# ESPRELAYS.net
KiCad netlist of a schematic drawn in EAGLE
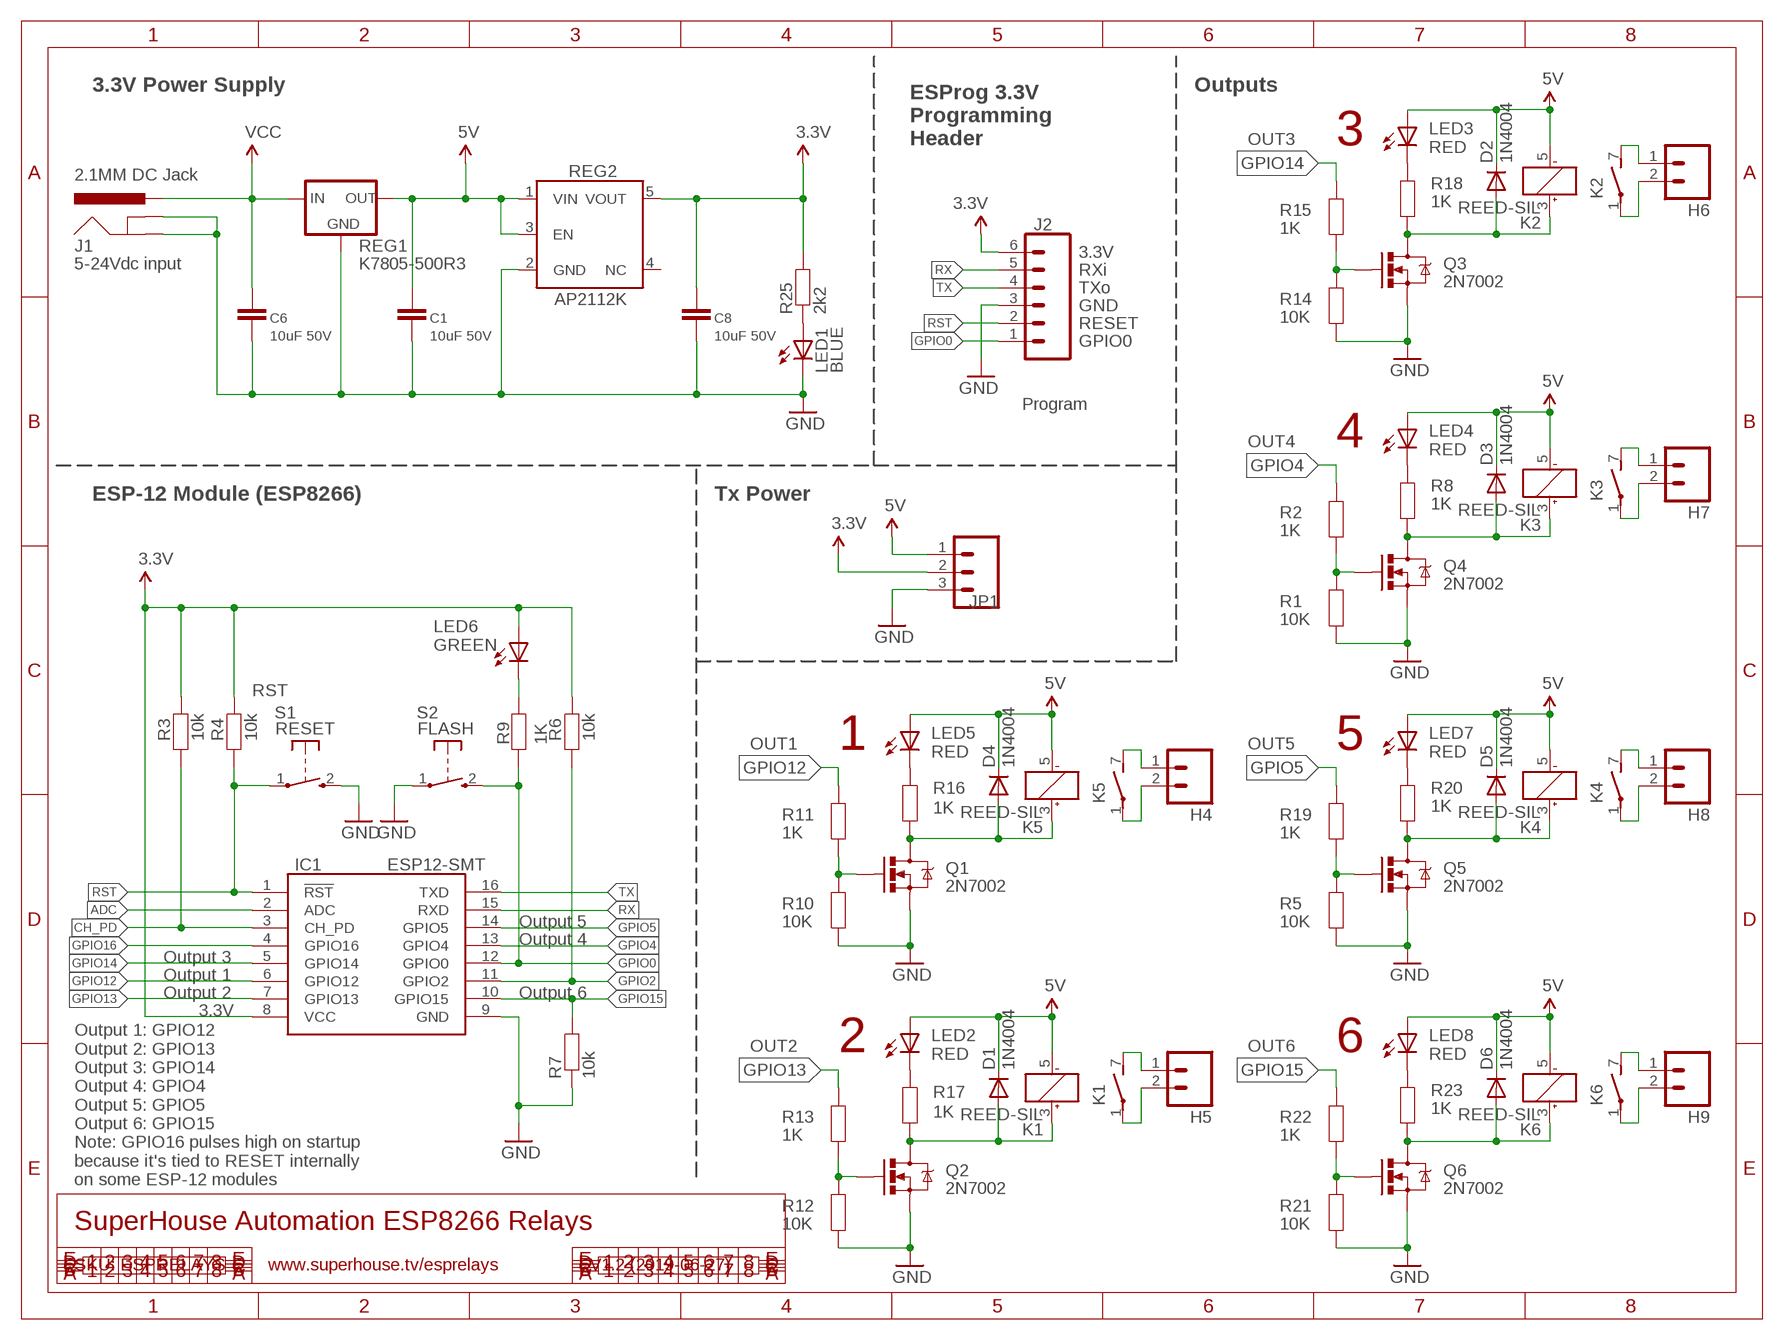
[diagram p0: schematic, sheet 1]

(export (version "E")
  (design (tool "Eeschema 10.0.6"))
  (components
    (comp (ref "C1")
      (value "10uF 50V")
      (footprint "eagle-import:C0805")
      (libsource (lib "eagle-import") (part "CAP0805"))
    )
    (comp (ref "C6")
      (value "10uF 50V")
      (footprint "eagle-import:C0805")
      (libsource (lib "eagle-import") (part "CAP0805"))
    )
    (comp (ref "C8")
      (value "10uF 50V")
      (footprint "eagle-import:C0805")
      (libsource (lib "eagle-import") (part "CAP0805"))
    )
    (comp (ref "D1")
      (value "1N4004")
      (footprint "eagle-import:SMA-DIODE")
      (libsource (lib "eagle-import") (part "DIODESMA"))
    )
    (comp (ref "D2")
      (value "1N4004")
      (footprint "eagle-import:SMA-DIODE")
      (libsource (lib "eagle-import") (part "DIODESMA"))
    )
    (comp (ref "D3")
      (value "1N4004")
      (footprint "eagle-import:SMA-DIODE")
      (libsource (lib "eagle-import") (part "DIODESMA"))
    )
    (comp (ref "D4")
      (value "1N4004")
      (footprint "eagle-import:SMA-DIODE")
      (libsource (lib "eagle-import") (part "DIODESMA"))
    )
    (comp (ref "D5")
      (value "1N4004")
      (footprint "eagle-import:SMA-DIODE")
      (libsource (lib "eagle-import") (part "DIODESMA"))
    )
    (comp (ref "D6")
      (value "1N4004")
      (footprint "eagle-import:SMA-DIODE")
      (libsource (lib "eagle-import") (part "DIODESMA"))
    )
    (comp (ref "H4")
      (value "M02-PIN")
      (footprint "eagle-import:1X02-P")
      (libsource (lib "eagle-import") (part "M02-PIN"))
    )
    (comp (ref "H5")
      (value "M02-PIN")
      (footprint "eagle-import:1X02-P")
      (libsource (lib "eagle-import") (part "M02-PIN"))
    )
    (comp (ref "H6")
      (value "M02-PIN")
      (footprint "eagle-import:1X02-P")
      (libsource (lib "eagle-import") (part "M02-PIN"))
    )
    (comp (ref "H7")
      (value "M02-PIN")
      (footprint "eagle-import:1X02-P")
      (libsource (lib "eagle-import") (part "M02-PIN"))
    )
    (comp (ref "H8")
      (value "M02-PIN")
      (footprint "eagle-import:1X02-P")
      (libsource (lib "eagle-import") (part "M02-PIN"))
    )
    (comp (ref "H9")
      (value "M02-PIN")
      (footprint "eagle-import:1X02-P")
      (libsource (lib "eagle-import") (part "M02-PIN"))
    )
    (comp (ref "IC1")
      (value "ESP12-SMT")
      (footprint "eagle-import:ESP12")
      (libsource (lib "eagle-import") (part "ESP12-SMT"))
    )
    (comp (ref "J1")
      (value "2.1MM DC Jack")
      (footprint "eagle-import:POWER_JACK_SLOTS")
      (libsource (lib "eagle-import") (part "POWER_JACK-SLOTS"))
    )
    (comp (ref "J2")
      (value "Program")
      (footprint "eagle-import:1X06-S")
      (libsource (lib "eagle-import") (part "M06-SOCKET"))
    )
    (comp (ref "JP1")
      (value "M03-PLAIN")
      (footprint "eagle-import:1X03")
      (libsource (lib "eagle-import") (part "M03-PLAIN"))
    )
    (comp (ref "K1")
      (value "REED-SIL")
      (footprint "eagle-import:REED")
      (libsource (lib "eagle-import") (part "REED-SIL"))
    )
    (comp (ref "K2")
      (value "REED-SIL")
      (footprint "eagle-import:REED")
      (libsource (lib "eagle-import") (part "REED-SIL"))
    )
    (comp (ref "K3")
      (value "REED-SIL")
      (footprint "eagle-import:REED")
      (libsource (lib "eagle-import") (part "REED-SIL"))
    )
    (comp (ref "K4")
      (value "REED-SIL")
      (footprint "eagle-import:REED")
      (libsource (lib "eagle-import") (part "REED-SIL"))
    )
    (comp (ref "K5")
      (value "REED-SIL")
      (footprint "eagle-import:REED")
      (libsource (lib "eagle-import") (part "REED-SIL"))
    )
    (comp (ref "K6")
      (value "REED-SIL")
      (footprint "eagle-import:REED")
      (libsource (lib "eagle-import") (part "REED-SIL"))
    )
    (comp (ref "LED1")
      (value "BLUE")
      (footprint "eagle-import:LED-0603")
      (libsource (lib "eagle-import") (part "LED0603"))
    )
    (comp (ref "LED2")
      (value "RED")
      (footprint "eagle-import:LED-0603")
      (libsource (lib "eagle-import") (part "LED0603"))
    )
    (comp (ref "LED3")
      (value "RED")
      (footprint "eagle-import:LED-0603")
      (libsource (lib "eagle-import") (part "LED0603"))
    )
    (comp (ref "LED4")
      (value "RED")
      (footprint "eagle-import:LED-0603")
      (libsource (lib "eagle-import") (part "LED0603"))
    )
    (comp (ref "LED5")
      (value "RED")
      (footprint "eagle-import:LED-0603")
      (libsource (lib "eagle-import") (part "LED0603"))
    )
    (comp (ref "LED6")
      (value "GREEN")
      (footprint "eagle-import:LED-0603")
      (libsource (lib "eagle-import") (part "LED0603"))
    )
    (comp (ref "LED7")
      (value "RED")
      (footprint "eagle-import:LED-0603")
      (libsource (lib "eagle-import") (part "LED0603"))
    )
    (comp (ref "LED8")
      (value "RED")
      (footprint "eagle-import:LED-0603")
      (libsource (lib "eagle-import") (part "LED0603"))
    )
    (comp (ref "Q1")
      (value "2N7002")
      (footprint "eagle-import:SOT23-3")
      (libsource (lib "eagle-import") (part "MOSFET-NCHANNELSMD"))
    )
    (comp (ref "Q2")
      (value "2N7002")
      (footprint "eagle-import:SOT23-3")
      (libsource (lib "eagle-import") (part "MOSFET-NCHANNELSMD"))
    )
    (comp (ref "Q3")
      (value "2N7002")
      (footprint "eagle-import:SOT23-3")
      (libsource (lib "eagle-import") (part "MOSFET-NCHANNELSMD"))
    )
    (comp (ref "Q4")
      (value "2N7002")
      (footprint "eagle-import:SOT23-3")
      (libsource (lib "eagle-import") (part "MOSFET-NCHANNELSMD"))
    )
    (comp (ref "Q5")
      (value "2N7002")
      (footprint "eagle-import:SOT23-3")
      (libsource (lib "eagle-import") (part "MOSFET-NCHANNELSMD"))
    )
    (comp (ref "Q6")
      (value "2N7002")
      (footprint "eagle-import:SOT23-3")
      (libsource (lib "eagle-import") (part "MOSFET-NCHANNELSMD"))
    )
    (comp (ref "R1")
      (value "10K")
      (footprint "eagle-import:R0603")
      (libsource (lib "eagle-import") (part "RESISTOR0603"))
    )
    (comp (ref "R2")
      (value "1K")
      (footprint "eagle-import:R0603")
      (libsource (lib "eagle-import") (part "RESISTOR0603"))
    )
    (comp (ref "R3")
      (value "10k")
      (footprint "eagle-import:R0603")
      (libsource (lib "eagle-import") (part "RESISTOR0603"))
    )
    (comp (ref "R4")
      (value "10k")
      (footprint "eagle-import:R0603")
      (libsource (lib "eagle-import") (part "RESISTOR0603"))
    )
    (comp (ref "R5")
      (value "10K")
      (footprint "eagle-import:R0603")
      (libsource (lib "eagle-import") (part "RESISTOR0603"))
    )
    (comp (ref "R6")
      (value "10k")
      (footprint "eagle-import:R0603")
      (libsource (lib "eagle-import") (part "RESISTOR0603"))
    )
    (comp (ref "R7")
      (value "10k")
      (footprint "eagle-import:R0603")
      (libsource (lib "eagle-import") (part "RESISTOR0603"))
    )
    (comp (ref "R8")
      (value "1K")
      (footprint "eagle-import:R0603")
      (libsource (lib "eagle-import") (part "RESISTOR0603"))
    )
    (comp (ref "R9")
      (value "1K")
      (footprint "eagle-import:R0603")
      (libsource (lib "eagle-import") (part "RESISTOR0603"))
    )
    (comp (ref "R10")
      (value "10K")
      (footprint "eagle-import:R0603")
      (libsource (lib "eagle-import") (part "RESISTOR0603"))
    )
    (comp (ref "R11")
      (value "1K")
      (footprint "eagle-import:R0603")
      (libsource (lib "eagle-import") (part "RESISTOR0603"))
    )
    (comp (ref "R12")
      (value "10K")
      (footprint "eagle-import:R0603")
      (libsource (lib "eagle-import") (part "RESISTOR0603"))
    )
    (comp (ref "R13")
      (value "1K")
      (footprint "eagle-import:R0603")
      (libsource (lib "eagle-import") (part "RESISTOR0603"))
    )
    (comp (ref "R14")
      (value "10K")
      (footprint "eagle-import:R0603")
      (libsource (lib "eagle-import") (part "RESISTOR0603"))
    )
    (comp (ref "R15")
      (value "1K")
      (footprint "eagle-import:R0603")
      (libsource (lib "eagle-import") (part "RESISTOR0603"))
    )
    (comp (ref "R16")
      (value "1K")
      (footprint "eagle-import:R0603")
      (libsource (lib "eagle-import") (part "RESISTOR0603"))
    )
    (comp (ref "R17")
      (value "1K")
      (footprint "eagle-import:R0603")
      (libsource (lib "eagle-import") (part "RESISTOR0603"))
    )
    (comp (ref "R18")
      (value "1K")
      (footprint "eagle-import:R0603")
      (libsource (lib "eagle-import") (part "RESISTOR0603"))
    )
    (comp (ref "R19")
      (value "1K")
      (footprint "eagle-import:R0603")
      (libsource (lib "eagle-import") (part "RESISTOR0603"))
    )
    (comp (ref "R20")
      (value "1K")
      (footprint "eagle-import:R0603")
      (libsource (lib "eagle-import") (part "RESISTOR0603"))
    )
    (comp (ref "R21")
      (value "10K")
      (footprint "eagle-import:R0603")
      (libsource (lib "eagle-import") (part "RESISTOR0603"))
    )
    (comp (ref "R22")
      (value "1K")
      (footprint "eagle-import:R0603")
      (libsource (lib "eagle-import") (part "RESISTOR0603"))
    )
    (comp (ref "R23")
      (value "1K")
      (footprint "eagle-import:R0603")
      (libsource (lib "eagle-import") (part "RESISTOR0603"))
    )
    (comp (ref "R25")
      (value "2k2")
      (footprint "eagle-import:R0603")
      (libsource (lib "eagle-import") (part "RESISTOR0603"))
    )
    (comp (ref "REG1")
      (value "K7805-500R3")
      (footprint "eagle-import:K78XX-500R3")
      (libsource (lib "eagle-import") (part "K78XX-500R3"))
    )
    (comp (ref "REG2")
      (value "AP2112KSOT25")
      (footprint "eagle-import:SOT23-5")
      (libsource (lib "eagle-import") (part "AP2112KSOT25"))
    )
    (comp (ref "S1")
      (value "RESET")
      (footprint "eagle-import:TACTILE_SMD_3X4X2")
      (libsource (lib "eagle-import") (part "TAC_SWITCH_2PINSMT"))
    )
    (comp (ref "S2")
      (value "FLASH")
      (footprint "eagle-import:TACTILE_SMD_3X4X2")
      (libsource (lib "eagle-import") (part "TAC_SWITCH_2PINSMT"))
    )
  )
  (nets
    (net (code "1") (name "/OUT1") (class "Default")
      (node (ref "D4") (pin "A") (pinfunction "A_A") (pintype "passive"))
      (node (ref "K5") (pin "3") (pinfunction "+_3") (pintype "passive"))
      (node (ref "Q1") (pin "3") (pinfunction "D_3") (pintype "passive"))
      (node (ref "R16") (pin "2") (pinfunction "2_2") (pintype "passive"))
    )
    (net (code "2") (name "/OUT2") (class "Default")
      (node (ref "D1") (pin "A") (pinfunction "A_A") (pintype "passive"))
      (node (ref "K1") (pin "3") (pinfunction "+_3") (pintype "passive"))
      (node (ref "Q2") (pin "3") (pinfunction "D_3") (pintype "passive"))
      (node (ref "R17") (pin "2") (pinfunction "2_2") (pintype "passive"))
    )
    (net (code "3") (name "/OUT3") (class "Default")
      (node (ref "D2") (pin "A") (pinfunction "A_A") (pintype "passive"))
      (node (ref "K2") (pin "3") (pinfunction "+_3") (pintype "passive"))
      (node (ref "Q3") (pin "3") (pinfunction "D_3") (pintype "passive"))
      (node (ref "R18") (pin "2") (pinfunction "2_2") (pintype "passive"))
    )
    (net (code "4") (name "/OUT4") (class "Default")
      (node (ref "D3") (pin "A") (pinfunction "A_A") (pintype "passive"))
      (node (ref "K3") (pin "3") (pinfunction "+_3") (pintype "passive"))
      (node (ref "Q4") (pin "3") (pinfunction "D_3") (pintype "passive"))
      (node (ref "R8") (pin "2") (pinfunction "2_2") (pintype "passive"))
    )
    (net (code "5") (name "/OUT5") (class "Default")
      (node (ref "D5") (pin "A") (pinfunction "A_A") (pintype "passive"))
      (node (ref "K4") (pin "3") (pinfunction "+_3") (pintype "passive"))
      (node (ref "Q5") (pin "3") (pinfunction "D_3") (pintype "passive"))
      (node (ref "R20") (pin "2") (pinfunction "2_2") (pintype "passive"))
    )
    (net (code "6") (name "/OUT6") (class "Default")
      (node (ref "D6") (pin "A") (pinfunction "A_A") (pintype "passive"))
      (node (ref "K6") (pin "3") (pinfunction "+_3") (pintype "passive"))
      (node (ref "Q6") (pin "3") (pinfunction "D_3") (pintype "passive"))
      (node (ref "R23") (pin "2") (pinfunction "2_2") (pintype "passive"))
    )
    (net (code "7") (name "3.3V") (class "Default")
      (node (ref "C8") (pin "1") (pinfunction "1_1") (pintype "passive"))
      (node (ref "IC1") (pin "8") (pinfunction "VCC_8") (pintype "power_in"))
      (node (ref "J2") (pin "6") (pinfunction "6_6") (pintype "passive"))
      (node (ref "JP1") (pin "2") (pinfunction "2_2") (pintype "passive"))
      (node (ref "LED6") (pin "A") (pinfunction "A_A") (pintype "passive"))
      (node (ref "R25") (pin "2") (pinfunction "2_2") (pintype "passive"))
      (node (ref "R3") (pin "2") (pinfunction "2_2") (pintype "passive"))
      (node (ref "R4") (pin "2") (pinfunction "2_2") (pintype "passive"))
      (node (ref "R6") (pin "2") (pinfunction "2_2") (pintype "passive"))
      (node (ref "REG2") (pin "5") (pinfunction "VOUT_5") (pintype "bidirectional"))
    )
    (net (code "8") (name "5V") (class "Default")
      (node (ref "C1") (pin "1") (pinfunction "1_1") (pintype "passive"))
      (node (ref "D1") (pin "C") (pinfunction "C_C") (pintype "passive"))
      (node (ref "D2") (pin "C") (pinfunction "C_C") (pintype "passive"))
      (node (ref "D3") (pin "C") (pinfunction "C_C") (pintype "passive"))
      (node (ref "D4") (pin "C") (pinfunction "C_C") (pintype "passive"))
      (node (ref "D5") (pin "C") (pinfunction "C_C") (pintype "passive"))
      (node (ref "D6") (pin "C") (pinfunction "C_C") (pintype "passive"))
      (node (ref "JP1") (pin "1") (pinfunction "1_1") (pintype "passive"))
      (node (ref "K1") (pin "5") (pinfunction "-_5") (pintype "passive"))
      (node (ref "K2") (pin "5") (pinfunction "-_5") (pintype "passive"))
      (node (ref "K3") (pin "5") (pinfunction "-_5") (pintype "passive"))
      (node (ref "K4") (pin "5") (pinfunction "-_5") (pintype "passive"))
      (node (ref "K5") (pin "5") (pinfunction "-_5") (pintype "passive"))
      (node (ref "K6") (pin "5") (pinfunction "-_5") (pintype "passive"))
      (node (ref "LED2") (pin "A") (pinfunction "A_A") (pintype "passive"))
      (node (ref "LED3") (pin "A") (pinfunction "A_A") (pintype "passive"))
      (node (ref "LED4") (pin "A") (pinfunction "A_A") (pintype "passive"))
      (node (ref "LED5") (pin "A") (pinfunction "A_A") (pintype "passive"))
      (node (ref "LED7") (pin "A") (pinfunction "A_A") (pintype "passive"))
      (node (ref "LED8") (pin "A") (pinfunction "A_A") (pintype "passive"))
      (node (ref "REG1") (pin "3") (pinfunction "OUT_3") (pintype "output"))
      (node (ref "REG2") (pin "1") (pinfunction "VIN_1") (pintype "bidirectional"))
      (node (ref "REG2") (pin "3") (pinfunction "EN_3") (pintype "bidirectional"))
    )
    (net (code "9") (name "ADC") (class "Default")
      (node (ref "IC1") (pin "2") (pinfunction "ADC_2") (pintype "input"))
    )
    (net (code "10") (name "CH_PD") (class "Default")
      (node (ref "IC1") (pin "3") (pinfunction "CH_PD_3") (pintype "input"))
      (node (ref "R3") (pin "1") (pinfunction "1_1") (pintype "passive"))
    )
    (net (code "11") (name "GND") (class "Default")
      (node (ref "C1") (pin "2") (pinfunction "2_2") (pintype "passive"))
      (node (ref "C6") (pin "2") (pinfunction "2_2") (pintype "passive"))
      (node (ref "C8") (pin "2") (pinfunction "2_2") (pintype "passive"))
      (node (ref "IC1") (pin "9") (pinfunction "GND_9") (pintype "power_in"))
      (node (ref "J1") (pin "GND") (pinfunction "GND_GND") (pintype "bidirectional"))
      (node (ref "J1") (pin "GNDBREAK") (pinfunction "GNDBREAK_GNDBREAK") (pintype "bidirectional"))
      (node (ref "J2") (pin "3") (pinfunction "3_3") (pintype "passive"))
      (node (ref "JP1") (pin "3") (pinfunction "3_3") (pintype "passive"))
      (node (ref "LED1") (pin "C") (pinfunction "C_C") (pintype "passive"))
      (node (ref "Q1") (pin "2") (pinfunction "S_2") (pintype "passive"))
      (node (ref "Q2") (pin "2") (pinfunction "S_2") (pintype "passive"))
      (node (ref "Q3") (pin "2") (pinfunction "S_2") (pintype "passive"))
      (node (ref "Q4") (pin "2") (pinfunction "S_2") (pintype "passive"))
      (node (ref "Q5") (pin "2") (pinfunction "S_2") (pintype "passive"))
      (node (ref "Q6") (pin "2") (pinfunction "S_2") (pintype "passive"))
      (node (ref "R1") (pin "1") (pinfunction "1_1") (pintype "passive"))
      (node (ref "R10") (pin "1") (pinfunction "1_1") (pintype "passive"))
      (node (ref "R12") (pin "1") (pinfunction "1_1") (pintype "passive"))
      (node (ref "R14") (pin "1") (pinfunction "1_1") (pintype "passive"))
      (node (ref "R21") (pin "1") (pinfunction "1_1") (pintype "passive"))
      (node (ref "R5") (pin "1") (pinfunction "1_1") (pintype "passive"))
      (node (ref "R7") (pin "1") (pinfunction "1_1") (pintype "passive"))
      (node (ref "REG1") (pin "2") (pinfunction "GND_2") (pintype "input"))
      (node (ref "REG2") (pin "2") (pinfunction "GND_2") (pintype "bidirectional"))
      (node (ref "S1") (pin "2") (pinfunction "S_2") (pintype "passive"))
      (node (ref "S2") (pin "1") (pinfunction "P_1") (pintype "passive"))
    )
    (net (code "12") (name "GPIO0") (class "Default")
      (node (ref "IC1") (pin "12") (pinfunction "GPIO0_12") (pintype "bidirectional"))
      (node (ref "J2") (pin "1") (pinfunction "1_1") (pintype "passive"))
      (node (ref "R9") (pin "2") (pinfunction "2_2") (pintype "passive"))
      (node (ref "S2") (pin "2") (pinfunction "S_2") (pintype "passive"))
    )
    (net (code "13") (name "GPIO2") (class "Default")
      (node (ref "IC1") (pin "11") (pinfunction "GPIO2_11") (pintype "bidirectional"))
      (node (ref "R6") (pin "1") (pinfunction "1_1") (pintype "passive"))
    )
    (net (code "14") (name "GPIO4") (class "Default")
      (node (ref "IC1") (pin "13") (pinfunction "GPIO4_13") (pintype "bidirectional"))
      (node (ref "R2") (pin "2") (pinfunction "2_2") (pintype "passive"))
    )
    (net (code "15") (name "GPIO5") (class "Default")
      (node (ref "IC1") (pin "14") (pinfunction "GPIO5_14") (pintype "bidirectional"))
      (node (ref "R19") (pin "2") (pinfunction "2_2") (pintype "passive"))
    )
    (net (code "16") (name "GPIO12") (class "Default")
      (node (ref "IC1") (pin "6") (pinfunction "GPIO12_6") (pintype "bidirectional"))
      (node (ref "R11") (pin "2") (pinfunction "2_2") (pintype "passive"))
    )
    (net (code "17") (name "GPIO13") (class "Default")
      (node (ref "IC1") (pin "7") (pinfunction "GPIO13_7") (pintype "bidirectional"))
      (node (ref "R13") (pin "2") (pinfunction "2_2") (pintype "passive"))
    )
    (net (code "18") (name "GPIO14") (class "Default")
      (node (ref "IC1") (pin "5") (pinfunction "GPIO14_5") (pintype "bidirectional"))
      (node (ref "R15") (pin "2") (pinfunction "2_2") (pintype "passive"))
    )
    (net (code "19") (name "GPIO15") (class "Default")
      (node (ref "IC1") (pin "10") (pinfunction "GPIO15_10") (pintype "bidirectional"))
      (node (ref "R22") (pin "2") (pinfunction "2_2") (pintype "passive"))
      (node (ref "R7") (pin "2") (pinfunction "2_2") (pintype "passive"))
    )
    (net (code "20") (name "GPIO16") (class "Default")
      (node (ref "IC1") (pin "4") (pinfunction "GPIO16_4") (pintype "bidirectional"))
    )
    (net (code "21") (name "Net-(K1B-P)") (class "Default")
      (node (ref "H5") (pin "2") (pinfunction "2_2") (pintype "passive"))
      (node (ref "K1") (pin "1") (pinfunction "P_1") (pintype "passive"))
    )
    (net (code "22") (name "Net-(K1B-S)") (class "Default")
      (node (ref "H5") (pin "1") (pinfunction "1_1") (pintype "passive"))
      (node (ref "K1") (pin "7") (pinfunction "S_7") (pintype "passive"))
    )
    (net (code "23") (name "Net-(K2B-P)") (class "Default")
      (node (ref "H6") (pin "2") (pinfunction "2_2") (pintype "passive"))
      (node (ref "K2") (pin "1") (pinfunction "P_1") (pintype "passive"))
    )
    (net (code "24") (name "Net-(K2B-S)") (class "Default")
      (node (ref "H6") (pin "1") (pinfunction "1_1") (pintype "passive"))
      (node (ref "K2") (pin "7") (pinfunction "S_7") (pintype "passive"))
    )
    (net (code "25") (name "Net-(K3B-P)") (class "Default")
      (node (ref "H7") (pin "2") (pinfunction "2_2") (pintype "passive"))
      (node (ref "K3") (pin "1") (pinfunction "P_1") (pintype "passive"))
    )
    (net (code "26") (name "Net-(K3B-S)") (class "Default")
      (node (ref "H7") (pin "1") (pinfunction "1_1") (pintype "passive"))
      (node (ref "K3") (pin "7") (pinfunction "S_7") (pintype "passive"))
    )
    (net (code "27") (name "Net-(K4B-P)") (class "Default")
      (node (ref "H8") (pin "2") (pinfunction "2_2") (pintype "passive"))
      (node (ref "K4") (pin "1") (pinfunction "P_1") (pintype "passive"))
    )
    (net (code "28") (name "Net-(K4B-S)") (class "Default")
      (node (ref "H8") (pin "1") (pinfunction "1_1") (pintype "passive"))
      (node (ref "K4") (pin "7") (pinfunction "S_7") (pintype "passive"))
    )
    (net (code "29") (name "Net-(K5B-P)") (class "Default")
      (node (ref "H4") (pin "2") (pinfunction "2_2") (pintype "passive"))
      (node (ref "K5") (pin "1") (pinfunction "P_1") (pintype "passive"))
    )
    (net (code "30") (name "Net-(K5B-S)") (class "Default")
      (node (ref "H4") (pin "1") (pinfunction "1_1") (pintype "passive"))
      (node (ref "K5") (pin "7") (pinfunction "S_7") (pintype "passive"))
    )
    (net (code "31") (name "Net-(K6B-P)") (class "Default")
      (node (ref "H9") (pin "2") (pinfunction "2_2") (pintype "passive"))
      (node (ref "K6") (pin "1") (pinfunction "P_1") (pintype "passive"))
    )
    (net (code "32") (name "Net-(K6B-S)") (class "Default")
      (node (ref "H9") (pin "1") (pinfunction "1_1") (pintype "passive"))
      (node (ref "K6") (pin "7") (pinfunction "S_7") (pintype "passive"))
    )
    (net (code "33") (name "Net-(LED1-PadA)") (class "Default")
      (node (ref "LED1") (pin "A") (pinfunction "A_A") (pintype "passive"))
      (node (ref "R25") (pin "1") (pinfunction "1_1") (pintype "passive"))
    )
    (net (code "34") (name "Net-(LED2-PadC)") (class "Default")
      (node (ref "LED2") (pin "C") (pinfunction "C_C") (pintype "passive"))
      (node (ref "R17") (pin "1") (pinfunction "1_1") (pintype "passive"))
    )
    (net (code "35") (name "Net-(LED3-PadC)") (class "Default")
      (node (ref "LED3") (pin "C") (pinfunction "C_C") (pintype "passive"))
      (node (ref "R18") (pin "1") (pinfunction "1_1") (pintype "passive"))
    )
    (net (code "36") (name "Net-(LED4-PadC)") (class "Default")
      (node (ref "LED4") (pin "C") (pinfunction "C_C") (pintype "passive"))
      (node (ref "R8") (pin "1") (pinfunction "1_1") (pintype "passive"))
    )
    (net (code "37") (name "Net-(LED5-PadC)") (class "Default")
      (node (ref "LED5") (pin "C") (pinfunction "C_C") (pintype "passive"))
      (node (ref "R16") (pin "1") (pinfunction "1_1") (pintype "passive"))
    )
    (net (code "38") (name "Net-(LED6-PadC)") (class "Default")
      (node (ref "LED6") (pin "C") (pinfunction "C_C") (pintype "passive"))
      (node (ref "R9") (pin "1") (pinfunction "1_1") (pintype "passive"))
    )
    (net (code "39") (name "Net-(LED7-PadC)") (class "Default")
      (node (ref "LED7") (pin "C") (pinfunction "C_C") (pintype "passive"))
      (node (ref "R20") (pin "1") (pinfunction "1_1") (pintype "passive"))
    )
    (net (code "40") (name "Net-(LED8-PadC)") (class "Default")
      (node (ref "LED8") (pin "C") (pinfunction "C_C") (pintype "passive"))
      (node (ref "R23") (pin "1") (pinfunction "1_1") (pintype "passive"))
    )
    (net (code "41") (name "Net-(Q1-G)") (class "Default")
      (node (ref "Q1") (pin "1") (pinfunction "G_1") (pintype "passive"))
      (node (ref "R10") (pin "2") (pinfunction "2_2") (pintype "passive"))
      (node (ref "R11") (pin "1") (pinfunction "1_1") (pintype "passive"))
    )
    (net (code "42") (name "Net-(Q2-G)") (class "Default")
      (node (ref "Q2") (pin "1") (pinfunction "G_1") (pintype "passive"))
      (node (ref "R12") (pin "2") (pinfunction "2_2") (pintype "passive"))
      (node (ref "R13") (pin "1") (pinfunction "1_1") (pintype "passive"))
    )
    (net (code "43") (name "Net-(Q3-G)") (class "Default")
      (node (ref "Q3") (pin "1") (pinfunction "G_1") (pintype "passive"))
      (node (ref "R14") (pin "2") (pinfunction "2_2") (pintype "passive"))
      (node (ref "R15") (pin "1") (pinfunction "1_1") (pintype "passive"))
    )
    (net (code "44") (name "Net-(Q4-G)") (class "Default")
      (node (ref "Q4") (pin "1") (pinfunction "G_1") (pintype "passive"))
      (node (ref "R1") (pin "2") (pinfunction "2_2") (pintype "passive"))
      (node (ref "R2") (pin "1") (pinfunction "1_1") (pintype "passive"))
    )
    (net (code "45") (name "Net-(Q5-G)") (class "Default")
      (node (ref "Q5") (pin "1") (pinfunction "G_1") (pintype "passive"))
      (node (ref "R19") (pin "1") (pinfunction "1_1") (pintype "passive"))
      (node (ref "R5") (pin "2") (pinfunction "2_2") (pintype "passive"))
    )
    (net (code "46") (name "Net-(Q6-G)") (class "Default")
      (node (ref "Q6") (pin "1") (pinfunction "G_1") (pintype "passive"))
      (node (ref "R21") (pin "2") (pinfunction "2_2") (pintype "passive"))
      (node (ref "R22") (pin "1") (pinfunction "1_1") (pintype "passive"))
    )
    (net (code "47") (name "RST") (class "Default")
      (node (ref "IC1") (pin "1") (pinfunction "~{RST}_1") (pintype "bidirectional"))
      (node (ref "J2") (pin "2") (pinfunction "2_2") (pintype "passive"))
      (node (ref "R4") (pin "1") (pinfunction "1_1") (pintype "passive"))
      (node (ref "S1") (pin "1") (pinfunction "P_1") (pintype "passive"))
    )
    (net (code "48") (name "RX") (class "Default")
      (node (ref "IC1") (pin "15") (pinfunction "RXD_15") (pintype "input"))
      (node (ref "J2") (pin "5") (pinfunction "5_5") (pintype "passive"))
    )
    (net (code "49") (name "TX") (class "Default")
      (node (ref "IC1") (pin "16") (pinfunction "TXD_16") (pintype "output"))
      (node (ref "J2") (pin "4") (pinfunction "4_4") (pintype "passive"))
    )
    (net (code "50") (name "VCC") (class "Default")
      (node (ref "C6") (pin "1") (pinfunction "1_1") (pintype "passive"))
      (node (ref "J1") (pin "PWR") (pinfunction "PWR_PWR") (pintype "bidirectional"))
      (node (ref "REG1") (pin "1") (pinfunction "IN_1") (pintype "input"))
    )
    (net (code "51") (name "unconnected-(REG2-NC-Pad4)") (class "Default")
      (node (ref "REG2") (pin "4") (pinfunction "NC_4") (pintype "bidirectional"))
    )
  )
)
